# headers.net
KiCad netlist of a schematic drawn in Altium Designer
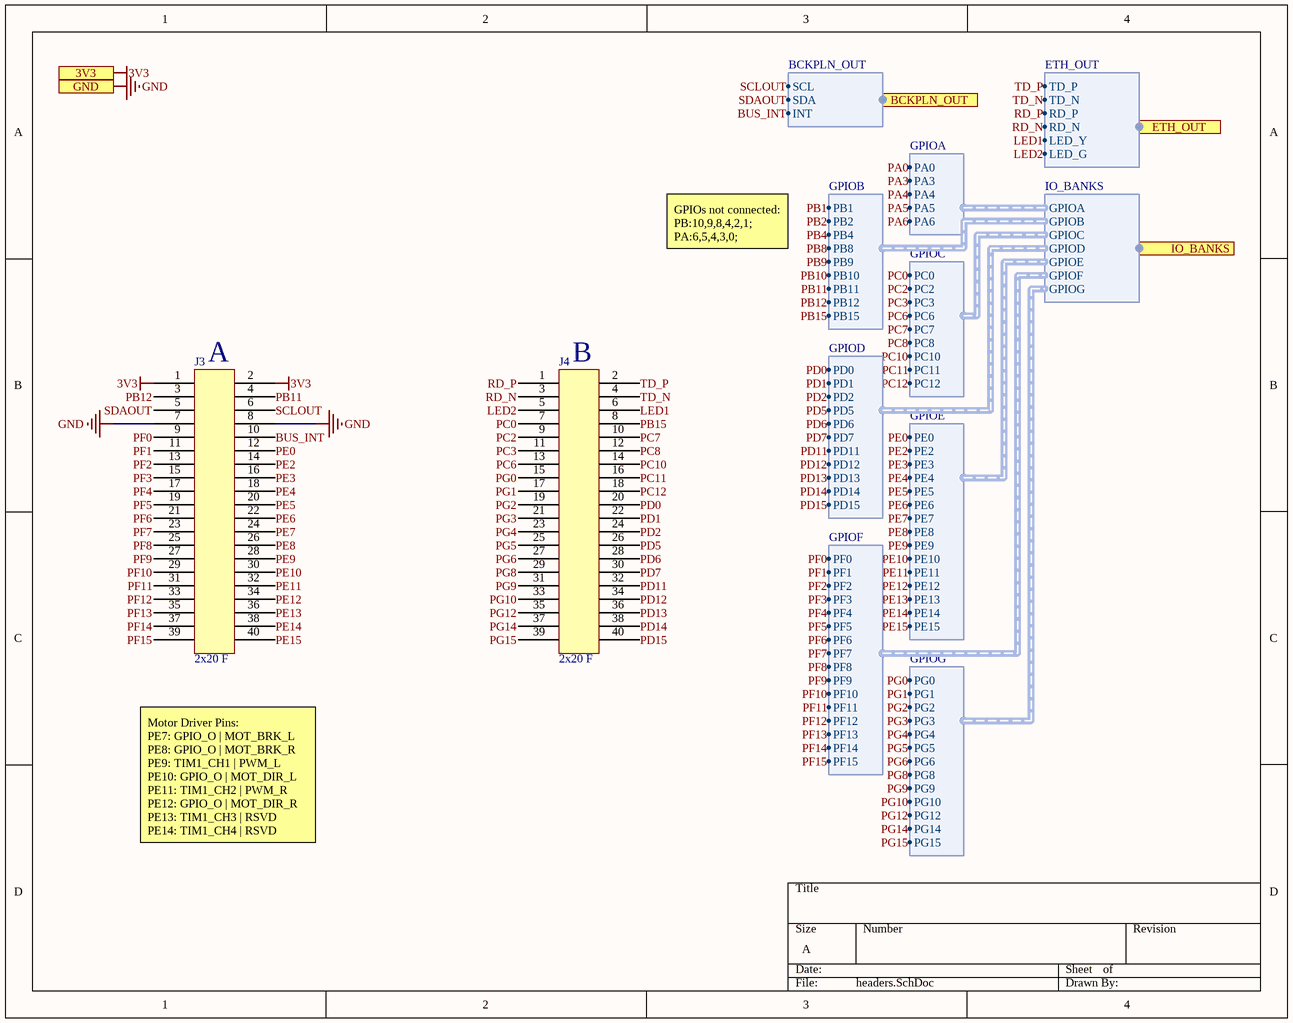
[diagram p0: headers.SchDoc]

(export (version "E")
  (design (tool "Eeschema 10.0.6"))
  (components
    (comp (ref "J3")
      (value "2x20 F")
      (footprint "CONN HDR 2x20 F BOT")
      (description "CONN Header 2x20 F")
      (libsource (lib "streetbot") (part "CONN Header 2x20 F"))
    )
    (comp (ref "J4")
      (value "2x20 F")
      (footprint "CONN HDR 2x20 F BOT")
      (description "CONN Header 2x20 F")
      (libsource (lib "streetbot") (part "CONN Header 2x20 F"))
    )
  )
  (nets
    (net (code "9") (name "/BUS_INT") (class "Default") (node (ref "J3") (pin "10") (pintype "passive")))
    (net (code "11") (name "/LED1") (class "Default") (node (ref "J4") (pin "6") (pintype "passive")))
    (net (code "12") (name "/LED2") (class "Default") (node (ref "J4") (pin "5") (pintype "passive")))
    (net (code "24") (name "/PB11") (class "Default") (node (ref "J3") (pin "4") (pintype "passive")))
    (net (code "25") (name "/PB12") (class "Default") (node (ref "J3") (pin "3") (pintype "passive")))
    (net (code "26") (name "/PB15") (class "Default") (node (ref "J4") (pin "8") (pintype "passive")))
    (net (code "27") (name "/PC0") (class "Default") (node (ref "J4") (pin "7") (pintype "passive")))
    (net (code "28") (name "/PC2") (class "Default") (node (ref "J4") (pin "9") (pintype "passive")))
    (net (code "29") (name "/PC3") (class "Default") (node (ref "J4") (pin "11") (pintype "passive")))
    (net (code "30") (name "/PC6") (class "Default") (node (ref "J4") (pin "13") (pintype "passive")))
    (net (code "31") (name "/PC7") (class "Default") (node (ref "J4") (pin "10") (pintype "passive")))
    (net (code "32") (name "/PC8") (class "Default") (node (ref "J4") (pin "12") (pintype "passive")))
    (net (code "33") (name "/PC10") (class "Default") (node (ref "J4") (pin "14") (pintype "passive")))
    (net (code "34") (name "/PC11") (class "Default") (node (ref "J4") (pin "16") (pintype "passive")))
    (net (code "35") (name "/PC12") (class "Default") (node (ref "J4") (pin "18") (pintype "passive")))
    (net (code "36") (name "/PD0") (class "Default") (node (ref "J4") (pin "20") (pintype "passive")))
    (net (code "37") (name "/PD1") (class "Default") (node (ref "J4") (pin "22") (pintype "passive")))
    (net (code "38") (name "/PD2") (class "Default") (node (ref "J4") (pin "24") (pintype "passive")))
    (net (code "39") (name "/PD5") (class "Default") (node (ref "J4") (pin "26") (pintype "passive")))
    (net (code "40") (name "/PD6") (class "Default") (node (ref "J4") (pin "28") (pintype "passive")))
    (net (code "41") (name "/PD7") (class "Default") (node (ref "J4") (pin "30") (pintype "passive")))
    (net (code "42") (name "/PD11") (class "Default") (node (ref "J4") (pin "32") (pintype "passive")))
    (net (code "43") (name "/PD12") (class "Default") (node (ref "J4") (pin "34") (pintype "passive")))
    (net (code "44") (name "/PD13") (class "Default") (node (ref "J4") (pin "36") (pintype "passive")))
    (net (code "45") (name "/PD14") (class "Default") (node (ref "J4") (pin "38") (pintype "passive")))
    (net (code "46") (name "/PD15") (class "Default") (node (ref "J4") (pin "40") (pintype "passive")))
    (net (code "47") (name "/PE0") (class "Default") (node (ref "J3") (pin "12") (pintype "passive")))
    (net (code "48") (name "/PE2") (class "Default") (node (ref "J3") (pin "14") (pintype "passive")))
    (net (code "49") (name "/PE3") (class "Default") (node (ref "J3") (pin "16") (pintype "passive")))
    (net (code "50") (name "/PE4") (class "Default") (node (ref "J3") (pin "18") (pintype "passive")))
    (net (code "51") (name "/PE5") (class "Default") (node (ref "J3") (pin "20") (pintype "passive")))
    (net (code "52") (name "/PE6") (class "Default") (node (ref "J3") (pin "22") (pintype "passive")))
    (net (code "53") (name "/PE7") (class "Default") (node (ref "J3") (pin "24") (pintype "passive")))
    (net (code "54") (name "/PE8") (class "Default") (node (ref "J3") (pin "26") (pintype "passive")))
    (net (code "55") (name "/PE9") (class "Default") (node (ref "J3") (pin "28") (pintype "passive")))
    (net (code "56") (name "/PE10") (class "Default") (node (ref "J3") (pin "30") (pintype "passive")))
    (net (code "57") (name "/PE11") (class "Default") (node (ref "J3") (pin "32") (pintype "passive")))
    (net (code "58") (name "/PE12") (class "Default") (node (ref "J3") (pin "34") (pintype "passive")))
    (net (code "59") (name "/PE13") (class "Default") (node (ref "J3") (pin "36") (pintype "passive")))
    (net (code "60") (name "/PE14") (class "Default") (node (ref "J3") (pin "38") (pintype "passive")))
    (net (code "61") (name "/PE15") (class "Default") (node (ref "J3") (pin "40") (pintype "passive")))
    (net (code "62") (name "/PF0") (class "Default") (node (ref "J3") (pin "9") (pintype "passive")))
    (net (code "63") (name "/PF1") (class "Default") (node (ref "J3") (pin "11") (pintype "passive")))
    (net (code "64") (name "/PF2") (class "Default") (node (ref "J3") (pin "13") (pintype "passive")))
    (net (code "65") (name "/PF3") (class "Default") (node (ref "J3") (pin "15") (pintype "passive")))
    (net (code "66") (name "/PF4") (class "Default") (node (ref "J3") (pin "17") (pintype "passive")))
    (net (code "67") (name "/PF5") (class "Default") (node (ref "J3") (pin "19") (pintype "passive")))
    (net (code "68") (name "/PF6") (class "Default") (node (ref "J3") (pin "21") (pintype "passive")))
    (net (code "69") (name "/PF7") (class "Default") (node (ref "J3") (pin "23") (pintype "passive")))
    (net (code "70") (name "/PF8") (class "Default") (node (ref "J3") (pin "25") (pintype "passive")))
    (net (code "71") (name "/PF9") (class "Default") (node (ref "J3") (pin "27") (pintype "passive")))
    (net (code "72") (name "/PF10") (class "Default") (node (ref "J3") (pin "29") (pintype "passive")))
    (net (code "73") (name "/PF11") (class "Default") (node (ref "J3") (pin "31") (pintype "passive")))
    (net (code "74") (name "/PF12") (class "Default") (node (ref "J3") (pin "33") (pintype "passive")))
    (net (code "75") (name "/PF13") (class "Default") (node (ref "J3") (pin "35") (pintype "passive")))
    (net (code "76") (name "/PF14") (class "Default") (node (ref "J3") (pin "37") (pintype "passive")))
    (net (code "77") (name "/PF15") (class "Default") (node (ref "J3") (pin "39") (pintype "passive")))
    (net (code "78") (name "/PG0") (class "Default") (node (ref "J4") (pin "15") (pintype "passive")))
    (net (code "79") (name "/PG1") (class "Default") (node (ref "J4") (pin "17") (pintype "passive")))
    (net (code "80") (name "/PG2") (class "Default") (node (ref "J4") (pin "19") (pintype "passive")))
    (net (code "81") (name "/PG3") (class "Default") (node (ref "J4") (pin "21") (pintype "passive")))
    (net (code "82") (name "/PG4") (class "Default") (node (ref "J4") (pin "23") (pintype "passive")))
    (net (code "83") (name "/PG5") (class "Default") (node (ref "J4") (pin "25") (pintype "passive")))
    (net (code "84") (name "/PG6") (class "Default") (node (ref "J4") (pin "27") (pintype "passive")))
    (net (code "85") (name "/PG8") (class "Default") (node (ref "J4") (pin "29") (pintype "passive")))
    (net (code "86") (name "/PG9") (class "Default") (node (ref "J4") (pin "31") (pintype "passive")))
    (net (code "87") (name "/PG10") (class "Default") (node (ref "J4") (pin "33") (pintype "passive")))
    (net (code "88") (name "/PG12") (class "Default") (node (ref "J4") (pin "35") (pintype "passive")))
    (net (code "89") (name "/PG14") (class "Default") (node (ref "J4") (pin "37") (pintype "passive")))
    (net (code "90") (name "/PG15") (class "Default") (node (ref "J4") (pin "39") (pintype "passive")))
    (net (code "91") (name "/RD_N") (class "Default") (node (ref "J4") (pin "3") (pintype "passive")))
    (net (code "92") (name "/RD_P") (class "Default") (node (ref "J4") (pin "1") (pintype "passive")))
    (net (code "93") (name "/SCLOUT") (class "Default") (node (ref "J3") (pin "6") (pintype "passive")))
    (net (code "94") (name "/SDAOUT") (class "Default") (node (ref "J3") (pin "5") (pintype "passive")))
    (net (code "95") (name "/TD_N") (class "Default") (node (ref "J4") (pin "4") (pintype "passive")))
    (net (code "96") (name "/TD_P") (class "Default") (node (ref "J4") (pin "2") (pintype "passive")))
    (net (code "104") (name "3V3") (class "Default")
      (node (ref "J3") (pin "1") (pintype "passive"))
      (node (ref "J3") (pin "2") (pintype "passive"))
    )
    (net (code "105") (name "GND") (class "Default")
      (node (ref "J3") (pin "7") (pintype "passive"))
      (node (ref "J3") (pin "8") (pintype "passive"))
    )
  )
)
